# sensorconductivity.net
KiCad netlist of a schematic drawn in EAGLE
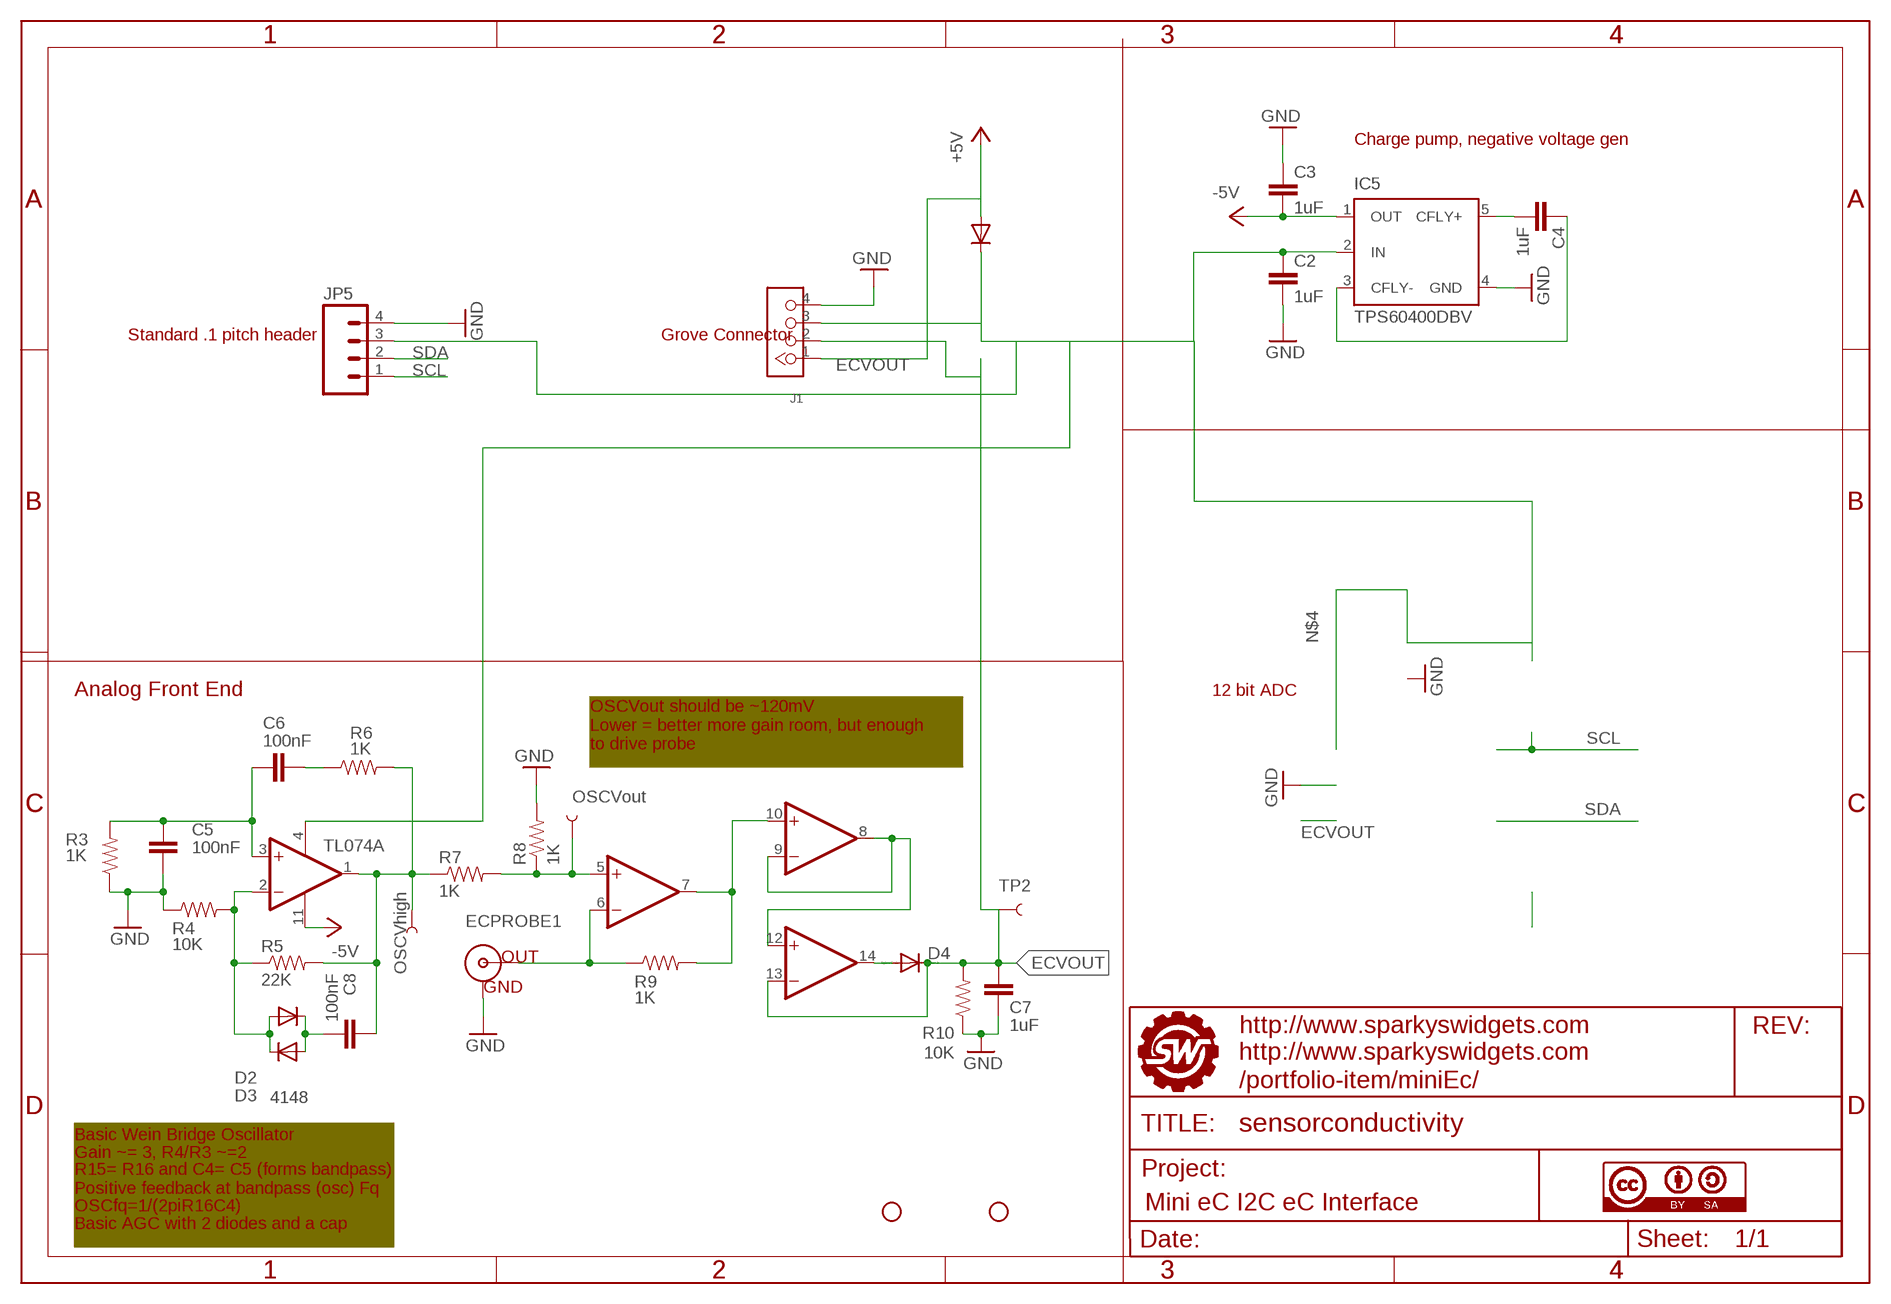
[diagram p0: schematic, sheet 1]

(export (version "E")
  (design (tool "Eeschema 10.0.6"))
  (components
    (comp (ref "C2")
      (value "1uF")
      (footprint "eagle-import:0805")
      (libsource (lib "eagle-import") (part "CAP0805"))
    )
    (comp (ref "C3")
      (value "1uF")
      (footprint "eagle-import:0805")
      (libsource (lib "eagle-import") (part "CAP0805"))
    )
    (comp (ref "C4")
      (value "1uF")
      (footprint "eagle-import:0805")
      (libsource (lib "eagle-import") (part "CAP0805"))
    )
    (comp (ref "C5")
      (value "100nF")
      (footprint "eagle-import:0805")
      (libsource (lib "eagle-import") (part "CAP0805"))
    )
    (comp (ref "C6")
      (value "100nF")
      (footprint "eagle-import:0805")
      (libsource (lib "eagle-import") (part "CAP0805"))
    )
    (comp (ref "C7")
      (value "1uF")
      (footprint "eagle-import:0805")
      (libsource (lib "eagle-import") (part "CAP0805"))
    )
    (comp (ref "C8")
      (value "100nF")
      (footprint "eagle-import:0805")
      (libsource (lib "eagle-import") (part "CAP0805"))
    )
    (comp (ref "D1")
      (value "4148")
      (footprint "eagle-import:SOD123")
      (libsource (lib "eagle-import") (part "MBR0520LT"))
    )
    (comp (ref "D2")
      (value "4148")
      (footprint "eagle-import:SOD123")
      (libsource (lib "eagle-import") (part "MBR0520LT"))
    )
    (comp (ref "D3")
      (value "4148")
      (footprint "eagle-import:SOD123")
      (libsource (lib "eagle-import") (part "MBR0520LT"))
    )
    (comp (ref "D4")
      (value "DIODE-SMB")
      (footprint "eagle-import:SMB")
      (libsource (lib "eagle-import") (part "DIODE-SMB"))
    )
    (comp (ref "ECPROBE1")
      (value "BNCPTH")
      (footprint "eagle-import:BNC")
      (libsource (lib "eagle-import") (part "BNCPTH"))
    )
    (comp (ref "IC5")
      (value "TPS60400DBV")
      (footprint "eagle-import:SOT23-DBV")
      (libsource (lib "eagle-import") (part "TPS60400DBV"))
    )
    (comp (ref "J1")
      (value "TWIG-4P-2.0-2.0")
      (footprint "eagle-import:4P-2.0")
      (libsource (lib "eagle-import") (part "TWIG-4P-2.0-2.0"))
    )
    (comp (ref "JP1")
      (value "STAND-OFF")
      (footprint "eagle-import:STAND-OFF")
      (libsource (lib "eagle-import") (part "STAND-OFF"))
    )
    (comp (ref "JP3")
      (value "STAND-OFF")
      (footprint "eagle-import:STAND-OFF")
      (libsource (lib "eagle-import") (part "STAND-OFF"))
    )
    (comp (ref "JP5")
      (value "M04PTH")
      (footprint "eagle-import:1X04")
      (libsource (lib "eagle-import") (part "M04PTH"))
    )
    (comp (ref "R3")
      (value "1K")
      (footprint "eagle-import:0805")
      (libsource (lib "eagle-import") (part "RESISTOR0805-RES"))
    )
    (comp (ref "R4")
      (value "10K")
      (footprint "eagle-import:0805")
      (libsource (lib "eagle-import") (part "RESISTOR0805-RES"))
    )
    (comp (ref "R5")
      (value "22K")
      (footprint "eagle-import:0805")
      (libsource (lib "eagle-import") (part "RESISTOR0805-RES"))
    )
    (comp (ref "R6")
      (value "1K")
      (footprint "eagle-import:0805")
      (libsource (lib "eagle-import") (part "RESISTOR0805-RES"))
    )
    (comp (ref "R7")
      (value "1K")
      (footprint "eagle-import:0805")
      (libsource (lib "eagle-import") (part "RESISTOR0805-RES"))
    )
    (comp (ref "R8")
      (value "1K")
      (footprint "eagle-import:0805")
      (libsource (lib "eagle-import") (part "RESISTOR0805-RES"))
    )
    (comp (ref "R9")
      (value "1K")
      (footprint "eagle-import:0805")
      (libsource (lib "eagle-import") (part "RESISTOR0805-RES"))
    )
    (comp (ref "R10")
      (value "10K")
      (footprint "eagle-import:0805")
      (libsource (lib "eagle-import") (part "RESISTOR0805-RES"))
    )
    (comp (ref "TL074")
      (value "TL074")
      (footprint "eagle-import:SO14")
      (libsource (lib "eagle-import") (part "QUADOPAMPM"))
    )
    (comp (ref "TP2")
      (value "TEST-POINT3")
      (footprint "eagle-import:PAD.03X.03")
      (libsource (lib "eagle-import") (part "TEST-POINT3"))
    )
    (comp (ref "TP3")
      (value "OSCVhigh")
      (footprint "eagle-import:PAD.03X.03")
      (libsource (lib "eagle-import") (part "TEST-POINT3"))
    )
    (comp (ref "TP5")
      (value "OSCVout")
      (footprint "eagle-import:PAD.03X.03")
      (libsource (lib "eagle-import") (part "TEST-POINT3"))
    )
    (comp (ref "U$4")
      (value "FRAME_MINIEC")
      (footprint "eagle-import:SWPCBLOGOWITHINFO")
      (fields
        (field (name "PROJECT") "Mini eC I2C eC Interface")
        (field (name "URL1") "/portfolio-item/miniEc/")
      )
      (libsource (lib "eagle-import") (part "FRAME_MINIEC"))
    )
    (comp (ref "U$5")
      (value "CC-BY-SA")
      (footprint "eagle-import:CC-BY-SA")
      (libsource (lib "eagle-import") (part "CC-BY-SA"))
    )
  )
  (nets
    (net (code "1") (name "+5V") (class "Default")
      (node (ref "D1") (pin "A") (pinfunction "A_A") (pintype "passive"))
      (node (ref "J1") (pin "1") (pinfunction "1_1") (pintype "bidirectional"))
    )
    (net (code "2") (name "-5V") (class "Default")
      (node (ref "C3") (pin "2") (pinfunction "2_2") (pintype "passive"))
      (node (ref "IC5") (pin "1") (pinfunction "OUT_1") (pintype "input"))
      (node (ref "TL074") (pin "11") (pinfunction "V-_11") (pintype "power_in"))
    )
    (net (code "3") (name "/N$4") (class "Default")
      (node (ref "C2") (pin "1") (pinfunction "1_1") (pintype "passive"))
      (node (ref "D1") (pin "C") (pinfunction "C_C") (pintype "passive"))
      (node (ref "IC5") (pin "2") (pinfunction "IN_2") (pintype "input"))
      (node (ref "J1") (pin "3") (pinfunction "3_3") (pintype "bidirectional"))
      (node (ref "JP5") (pin "3") (pinfunction "3_3") (pintype "passive"))
      (node (ref "TL074") (pin "4") (pinfunction "V+_4") (pintype "power_in"))
    )
    (net (code "4") (name "/SCL") (class "Default")
      (node (ref "JP5") (pin "1") (pinfunction "1_1") (pintype "passive"))
    )
    (net (code "5") (name "/SDA") (class "Default")
      (node (ref "JP5") (pin "2") (pinfunction "2_2") (pintype "passive"))
    )
    (net (code "6") (name "ECVOUT") (class "Default")
      (node (ref "C7") (pin "2") (pinfunction "2_2") (pintype "passive"))
      (node (ref "D4") (pin "C") (pinfunction "C_C") (pintype "passive"))
      (node (ref "J1") (pin "2") (pinfunction "2_2") (pintype "bidirectional"))
      (node (ref "R10") (pin "2") (pinfunction "2_2") (pintype "passive"))
      (node (ref "TL074") (pin "13") (pinfunction "-IN_13") (pintype "input"))
      (node (ref "TP2") (pin "P$1") (pinfunction "1_P$1") (pintype "bidirectional"))
    )
    (net (code "7") (name "GND") (class "Default")
      (node (ref "C2") (pin "2") (pinfunction "2_2") (pintype "passive"))
      (node (ref "C3") (pin "1") (pinfunction "1_1") (pintype "passive"))
      (node (ref "C5") (pin "1") (pinfunction "1_1") (pintype "passive"))
      (node (ref "C7") (pin "1") (pinfunction "1_1") (pintype "passive"))
      (node (ref "ECPROBE1") (pin "GND") (pinfunction "GND_GND") (pintype "bidirectional"))
      (node (ref "IC5") (pin "4") (pinfunction "GND_4") (pintype "passive"))
      (node (ref "J1") (pin "4") (pinfunction "4_4") (pintype "bidirectional"))
      (node (ref "JP5") (pin "4") (pinfunction "4_4") (pintype "passive"))
      (node (ref "R10") (pin "1") (pinfunction "1_1") (pintype "passive"))
      (node (ref "R3") (pin "1") (pinfunction "1_1") (pintype "passive"))
      (node (ref "R4") (pin "1") (pinfunction "1_1") (pintype "passive"))
      (node (ref "R8") (pin "2") (pinfunction "2_2") (pintype "passive"))
    )
    (net (code "8") (name "Net-(C6-Pad1)") (class "Default")
      (node (ref "C6") (pin "1") (pinfunction "1_1") (pintype "passive"))
      (node (ref "R6") (pin "1") (pinfunction "1_1") (pintype "passive"))
    )
    (net (code "9") (name "Net-(C8-Pad2)") (class "Default")
      (node (ref "C8") (pin "2") (pinfunction "2_2") (pintype "passive"))
      (node (ref "D2") (pin "C") (pinfunction "C_C") (pintype "passive"))
      (node (ref "D3") (pin "A") (pinfunction "A_A") (pintype "passive"))
    )
    (net (code "10") (name "Net-(ECPROBE1-OUT)") (class "Default")
      (node (ref "ECPROBE1") (pin "S") (pinfunction "OUT_S") (pintype "bidirectional"))
      (node (ref "R9") (pin "1") (pinfunction "1_1") (pintype "passive"))
      (node (ref "TL074") (pin "6") (pinfunction "-IN_6") (pintype "input"))
    )
    (net (code "11") (name "Net-(IC5-CFLY+)") (class "Default")
      (node (ref "C4") (pin "2") (pinfunction "2_2") (pintype "passive"))
      (node (ref "IC5") (pin "5") (pinfunction "CFLY+_5") (pintype "passive"))
    )
    (net (code "12") (name "Net-(IC5-CFLY-)") (class "Default")
      (node (ref "C4") (pin "1") (pinfunction "1_1") (pintype "passive"))
      (node (ref "IC5") (pin "3") (pinfunction "CFLY-_3") (pintype "power_in"))
    )
    (net (code "13") (name "Net-(TL074A-+IN)") (class "Default")
      (node (ref "C5") (pin "2") (pinfunction "2_2") (pintype "passive"))
      (node (ref "C6") (pin "2") (pinfunction "2_2") (pintype "passive"))
      (node (ref "R3") (pin "2") (pinfunction "2_2") (pintype "passive"))
      (node (ref "TL074") (pin "3") (pinfunction "+IN_3") (pintype "input"))
    )
    (net (code "14") (name "Net-(TL074A--IN)") (class "Default")
      (node (ref "D2") (pin "A") (pinfunction "A_A") (pintype "passive"))
      (node (ref "D3") (pin "C") (pinfunction "C_C") (pintype "passive"))
      (node (ref "R4") (pin "2") (pinfunction "2_2") (pintype "passive"))
      (node (ref "R5") (pin "1") (pinfunction "1_1") (pintype "passive"))
      (node (ref "TL074") (pin "2") (pinfunction "-IN_2") (pintype "input"))
    )
    (net (code "15") (name "Net-(TL074A-OUT)") (class "Default")
      (node (ref "C8") (pin "1") (pinfunction "1_1") (pintype "passive"))
      (node (ref "R5") (pin "2") (pinfunction "2_2") (pintype "passive"))
      (node (ref "R6") (pin "2") (pinfunction "2_2") (pintype "passive"))
      (node (ref "R7") (pin "1") (pinfunction "1_1") (pintype "passive"))
      (node (ref "TL074") (pin "1") (pinfunction "OUT_1") (pintype "output"))
      (node (ref "TP3") (pin "P$1") (pinfunction "1_P$1") (pintype "bidirectional"))
    )
    (net (code "16") (name "Net-(TL074B-+IN)") (class "Default")
      (node (ref "R7") (pin "2") (pinfunction "2_2") (pintype "passive"))
      (node (ref "R8") (pin "1") (pinfunction "1_1") (pintype "passive"))
      (node (ref "TL074") (pin "5") (pinfunction "+IN_5") (pintype "input"))
      (node (ref "TP5") (pin "P$1") (pinfunction "1_P$1") (pintype "bidirectional"))
    )
    (net (code "17") (name "Net-(TL074B-OUT)") (class "Default")
      (node (ref "R9") (pin "2") (pinfunction "2_2") (pintype "passive"))
      (node (ref "TL074") (pin "10") (pinfunction "+IN_10") (pintype "input"))
      (node (ref "TL074") (pin "7") (pinfunction "OUT_7") (pintype "output"))
    )
    (net (code "18") (name "Net-(TL074C--IN)") (class "Default")
      (node (ref "TL074") (pin "12") (pinfunction "+IN_12") (pintype "input"))
      (node (ref "TL074") (pin "8") (pinfunction "OUT_8") (pintype "output"))
      (node (ref "TL074") (pin "9") (pinfunction "-IN_9") (pintype "input"))
    )
    (net (code "19") (name "Net-(TL074D-OUT)") (class "Default")
      (node (ref "D4") (pin "A") (pinfunction "A_A") (pintype "passive"))
      (node (ref "TL074") (pin "14") (pinfunction "OUT_14") (pintype "output"))
    )
  )
)
